# RaspiConnection.net
KiCad netlist of a schematic drawn in Altium Designer
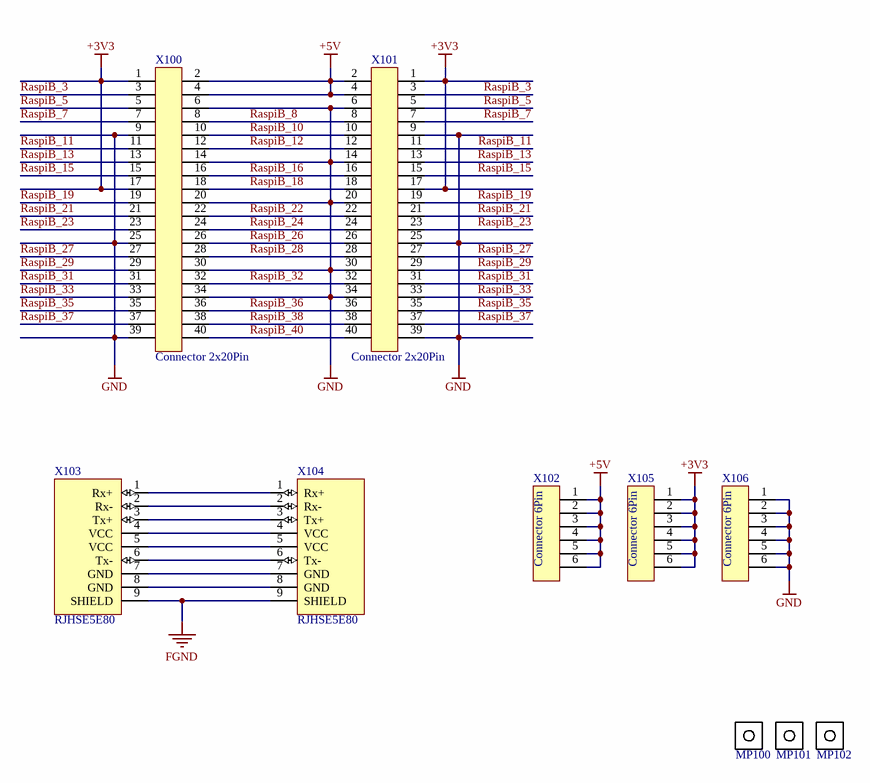
[diagram p0: RaspiConnection.SchDoc]

(export (version "E")
  (design (tool "Eeschema 10.0.6"))
  (components
    (comp (ref "MP100")
      (value "Mounting Hole")
      (footprint "M3x08S")
      (description "Different Mounting holes")
      (libsource (lib "CyberDeck") (part "MP_Mounting Hole"))
    )
    (comp (ref "MP101")
      (value "Mounting Hole")
      (footprint "M3x08S")
      (description "Different Mounting holes")
      (libsource (lib "CyberDeck") (part "MP_Mounting Hole"))
    )
    (comp (ref "MP102")
      (value "Mounting Hole")
      (footprint "M3x08S")
      (description "Different Mounting holes")
      (libsource (lib "CyberDeck") (part "MP_Mounting Hole"))
    )
    (comp (ref "X100")
      (value "Connector 2x20Pin")
      (footprint "Pin Header 2x20 TH Pitch 2.54mm - sh")
      (description "Generic connector 2x20 Pin")
      (libsource (lib "CyberDeck") (part "X_Connector 2x20Pin"))
    )
    (comp (ref "X101")
      (value "Connector 2x20Pin")
      (footprint "Pin Header 2x20 SMD Pitch 2.54mm F")
      (description "Generic connector 2x20 Pin")
      (libsource (lib "CyberDeck") (part "X_Connector 2x20Pin_1"))
    )
    (comp (ref "X102")
      (value "Connector 6Pin")
      (footprint "Pin Header 1x6 TH Pitch 2.54mm")
      (description "Generic connector 6 Pin")
      (libsource (lib "Cyberdeck") (part "X_Connector 6Pin"))
    )
    (comp (ref "X103")
      (value "RJHSE5E80")
      (footprint "RJ45")
      (description "Modular Connectors / Ethernet Connectors High Speed RJ w/no LED's or Shield")
      (libsource (lib "CyberDeck") (part "X_RJHSE5E80"))
    )
    (comp (ref "X104")
      (value "RJHSE5E80")
      (footprint "RJ45")
      (description "Modular Connectors / Ethernet Connectors High Speed RJ w/no LED's or Shield")
      (libsource (lib "") (part "X_RJHSE5E80_1"))
    )
    (comp (ref "X105")
      (value "Connector 6Pin")
      (footprint "Pin Header 1x6 TH Pitch 2.54mm")
      (description "Generic connector 6 Pin")
      (libsource (lib "Cyberdeck") (part "X_Connector 6Pin"))
    )
    (comp (ref "X106")
      (value "Connector 6Pin")
      (footprint "Pin Header 1x6 TH Pitch 2.54mm")
      (description "Generic connector 6 Pin")
      (libsource (lib "Cyberdeck") (part "X_Connector 6Pin"))
    )
  )
  (nets
    (net (code "1") (name "+3V3") (class "Default")
      (node (ref "X100") (pin "1") (pintype "passive"))
      (node (ref "X100") (pin "17") (pintype "passive"))
      (node (ref "X101") (pin "1") (pintype "passive"))
      (node (ref "X101") (pin "17") (pintype "passive"))
      (node (ref "X105") (pin "1") (pintype "passive"))
      (node (ref "X105") (pin "2") (pintype "passive"))
      (node (ref "X105") (pin "3") (pintype "passive"))
      (node (ref "X105") (pin "4") (pintype "passive"))
      (node (ref "X105") (pin "5") (pintype "passive"))
      (node (ref "X105") (pin "6") (pintype "passive"))
    )
    (net (code "2") (name "+5V") (class "Default")
      (node (ref "X100") (pin "2") (pintype "passive"))
      (node (ref "X100") (pin "4") (pintype "passive"))
      (node (ref "X101") (pin "2") (pintype "passive"))
      (node (ref "X101") (pin "4") (pintype "passive"))
      (node (ref "X102") (pin "1") (pintype "passive"))
      (node (ref "X102") (pin "2") (pintype "passive"))
      (node (ref "X102") (pin "3") (pintype "passive"))
      (node (ref "X102") (pin "4") (pintype "passive"))
      (node (ref "X102") (pin "5") (pintype "passive"))
      (node (ref "X102") (pin "6") (pintype "passive"))
    )
    (net (code "3") (name "/RaspiB_3") (class "Default")
      (node (ref "X100") (pin "3") (pintype "passive"))
      (node (ref "X101") (pin "3") (pintype "passive"))
    )
    (net (code "4") (name "/RaspiB_5") (class "Default")
      (node (ref "X100") (pin "5") (pintype "passive"))
      (node (ref "X101") (pin "5") (pintype "passive"))
    )
    (net (code "5") (name "/RaspiB_7") (class "Default")
      (node (ref "X100") (pin "7") (pintype "passive"))
      (node (ref "X101") (pin "7") (pintype "passive"))
    )
    (net (code "6") (name "/RaspiB_8") (class "Default")
      (node (ref "X100") (pin "8") (pintype "passive"))
      (node (ref "X101") (pin "8") (pintype "passive"))
    )
    (net (code "7") (name "/RaspiB_10") (class "Default")
      (node (ref "X100") (pin "10") (pintype "passive"))
      (node (ref "X101") (pin "10") (pintype "passive"))
    )
    (net (code "8") (name "/RaspiB_11") (class "Default")
      (node (ref "X100") (pin "11") (pintype "passive"))
      (node (ref "X101") (pin "11") (pintype "passive"))
    )
    (net (code "9") (name "/RaspiB_12") (class "Default")
      (node (ref "X100") (pin "12") (pintype "passive"))
      (node (ref "X101") (pin "12") (pintype "passive"))
    )
    (net (code "10") (name "/RaspiB_13") (class "Default")
      (node (ref "X100") (pin "13") (pintype "passive"))
      (node (ref "X101") (pin "13") (pintype "passive"))
    )
    (net (code "11") (name "/RaspiB_15") (class "Default")
      (node (ref "X100") (pin "15") (pintype "passive"))
      (node (ref "X101") (pin "15") (pintype "passive"))
    )
    (net (code "12") (name "/RaspiB_16") (class "Default")
      (node (ref "X100") (pin "16") (pintype "passive"))
      (node (ref "X101") (pin "16") (pintype "passive"))
    )
    (net (code "13") (name "/RaspiB_18") (class "Default")
      (node (ref "X100") (pin "18") (pintype "passive"))
      (node (ref "X101") (pin "18") (pintype "passive"))
    )
    (net (code "14") (name "/RaspiB_19") (class "Default")
      (node (ref "X100") (pin "19") (pintype "passive"))
      (node (ref "X101") (pin "19") (pintype "passive"))
    )
    (net (code "15") (name "/RaspiB_21") (class "Default")
      (node (ref "X100") (pin "21") (pintype "passive"))
      (node (ref "X101") (pin "21") (pintype "passive"))
    )
    (net (code "16") (name "/RaspiB_22") (class "Default")
      (node (ref "X100") (pin "22") (pintype "passive"))
      (node (ref "X101") (pin "22") (pintype "passive"))
    )
    (net (code "17") (name "/RaspiB_23") (class "Default")
      (node (ref "X100") (pin "23") (pintype "passive"))
      (node (ref "X101") (pin "23") (pintype "passive"))
    )
    (net (code "18") (name "/RaspiB_24") (class "Default")
      (node (ref "X100") (pin "24") (pintype "passive"))
      (node (ref "X101") (pin "24") (pintype "passive"))
    )
    (net (code "19") (name "/RaspiB_26") (class "Default")
      (node (ref "X100") (pin "26") (pintype "passive"))
      (node (ref "X101") (pin "26") (pintype "passive"))
    )
    (net (code "20") (name "/RaspiB_27") (class "Default")
      (node (ref "X100") (pin "27") (pintype "passive"))
      (node (ref "X101") (pin "27") (pintype "passive"))
    )
    (net (code "21") (name "/RaspiB_28") (class "Default")
      (node (ref "X100") (pin "28") (pintype "passive"))
      (node (ref "X101") (pin "28") (pintype "passive"))
    )
    (net (code "22") (name "/RaspiB_29") (class "Default")
      (node (ref "X100") (pin "29") (pintype "passive"))
      (node (ref "X101") (pin "29") (pintype "passive"))
    )
    (net (code "23") (name "/RaspiB_31") (class "Default")
      (node (ref "X100") (pin "31") (pintype "passive"))
      (node (ref "X101") (pin "31") (pintype "passive"))
    )
    (net (code "24") (name "/RaspiB_32") (class "Default")
      (node (ref "X100") (pin "32") (pintype "passive"))
      (node (ref "X101") (pin "32") (pintype "passive"))
    )
    (net (code "25") (name "/RaspiB_33") (class "Default")
      (node (ref "X100") (pin "33") (pintype "passive"))
      (node (ref "X101") (pin "33") (pintype "passive"))
    )
    (net (code "26") (name "/RaspiB_35") (class "Default")
      (node (ref "X100") (pin "35") (pintype "passive"))
      (node (ref "X101") (pin "35") (pintype "passive"))
    )
    (net (code "27") (name "/RaspiB_36") (class "Default")
      (node (ref "X100") (pin "36") (pintype "passive"))
      (node (ref "X101") (pin "36") (pintype "passive"))
    )
    (net (code "28") (name "/RaspiB_37") (class "Default")
      (node (ref "X100") (pin "37") (pintype "passive"))
      (node (ref "X101") (pin "37") (pintype "passive"))
    )
    (net (code "29") (name "/RaspiB_38") (class "Default")
      (node (ref "X100") (pin "38") (pintype "passive"))
      (node (ref "X101") (pin "38") (pintype "passive"))
    )
    (net (code "30") (name "/RaspiB_40") (class "Default")
      (node (ref "X100") (pin "40") (pintype "passive"))
      (node (ref "X101") (pin "40") (pintype "passive"))
    )
    (net (code "31") (name "FGND") (class "Default")
      (node (ref "X103") (pin "9") (pinfunction "SHIELD_9") (pintype "power_in"))
      (node (ref "X104") (pin "9") (pinfunction "SHIELD_9") (pintype "power_in"))
    )
    (net (code "32") (name "GND") (class "Default")
      (node (ref "X100") (pin "14") (pintype "passive"))
      (node (ref "X100") (pin "20") (pintype "passive"))
      (node (ref "X100") (pin "25") (pintype "passive"))
      (node (ref "X100") (pin "30") (pintype "passive"))
      (node (ref "X100") (pin "34") (pintype "passive"))
      (node (ref "X100") (pin "39") (pintype "passive"))
      (node (ref "X100") (pin "6") (pintype "passive"))
      (node (ref "X100") (pin "9") (pintype "passive"))
      (node (ref "X101") (pin "14") (pintype "passive"))
      (node (ref "X101") (pin "20") (pintype "passive"))
      (node (ref "X101") (pin "25") (pintype "passive"))
      (node (ref "X101") (pin "30") (pintype "passive"))
      (node (ref "X101") (pin "34") (pintype "passive"))
      (node (ref "X101") (pin "39") (pintype "passive"))
      (node (ref "X101") (pin "6") (pintype "passive"))
      (node (ref "X101") (pin "9") (pintype "passive"))
      (node (ref "X106") (pin "1") (pintype "passive"))
      (node (ref "X106") (pin "2") (pintype "passive"))
      (node (ref "X106") (pin "3") (pintype "passive"))
      (node (ref "X106") (pin "4") (pintype "passive"))
      (node (ref "X106") (pin "5") (pintype "passive"))
      (node (ref "X106") (pin "6") (pintype "passive"))
    )
    (net (code "33") (name "Net-(X103-GND-Pad7)") (class "Default")
      (node (ref "X103") (pin "7") (pinfunction "GND_7") (pintype "power_in"))
      (node (ref "X104") (pin "7") (pinfunction "GND_7") (pintype "power_in"))
    )
    (net (code "34") (name "Net-(X103-GND-Pad8)") (class "Default")
      (node (ref "X103") (pin "8") (pinfunction "GND_8") (pintype "power_in"))
      (node (ref "X104") (pin "8") (pinfunction "GND_8") (pintype "power_in"))
    )
    (net (code "35") (name "Net-(X103-Rx+)") (class "Default")
      (node (ref "X103") (pin "1") (pinfunction "Rx+_1") (pintype "bidirectional"))
      (node (ref "X104") (pin "1") (pinfunction "Rx+_1") (pintype "bidirectional"))
    )
    (net (code "36") (name "Net-(X103-Rx-)") (class "Default")
      (node (ref "X103") (pin "2") (pinfunction "Rx-_2") (pintype "bidirectional"))
      (node (ref "X104") (pin "2") (pinfunction "Rx-_2") (pintype "bidirectional"))
    )
    (net (code "37") (name "Net-(X103-Tx+)") (class "Default")
      (node (ref "X103") (pin "3") (pinfunction "Tx+_3") (pintype "bidirectional"))
      (node (ref "X104") (pin "3") (pinfunction "Tx+_3") (pintype "bidirectional"))
    )
    (net (code "38") (name "Net-(X103-Tx-)") (class "Default")
      (node (ref "X103") (pin "6") (pinfunction "Tx-_6") (pintype "bidirectional"))
      (node (ref "X104") (pin "6") (pinfunction "Tx-_6") (pintype "bidirectional"))
    )
    (net (code "39") (name "Net-(X103-VCC-Pad4)") (class "Default")
      (node (ref "X103") (pin "4") (pinfunction "VCC_4") (pintype "power_in"))
      (node (ref "X104") (pin "4") (pinfunction "VCC_4") (pintype "power_in"))
    )
    (net (code "40") (name "Net-(X103-VCC-Pad5)") (class "Default")
      (node (ref "X103") (pin "5") (pinfunction "VCC_5") (pintype "power_in"))
      (node (ref "X104") (pin "5") (pinfunction "VCC_5") (pintype "power_in"))
    )
  )
)
